# Power.net
KiCad netlist of a schematic drawn in Altium Designer
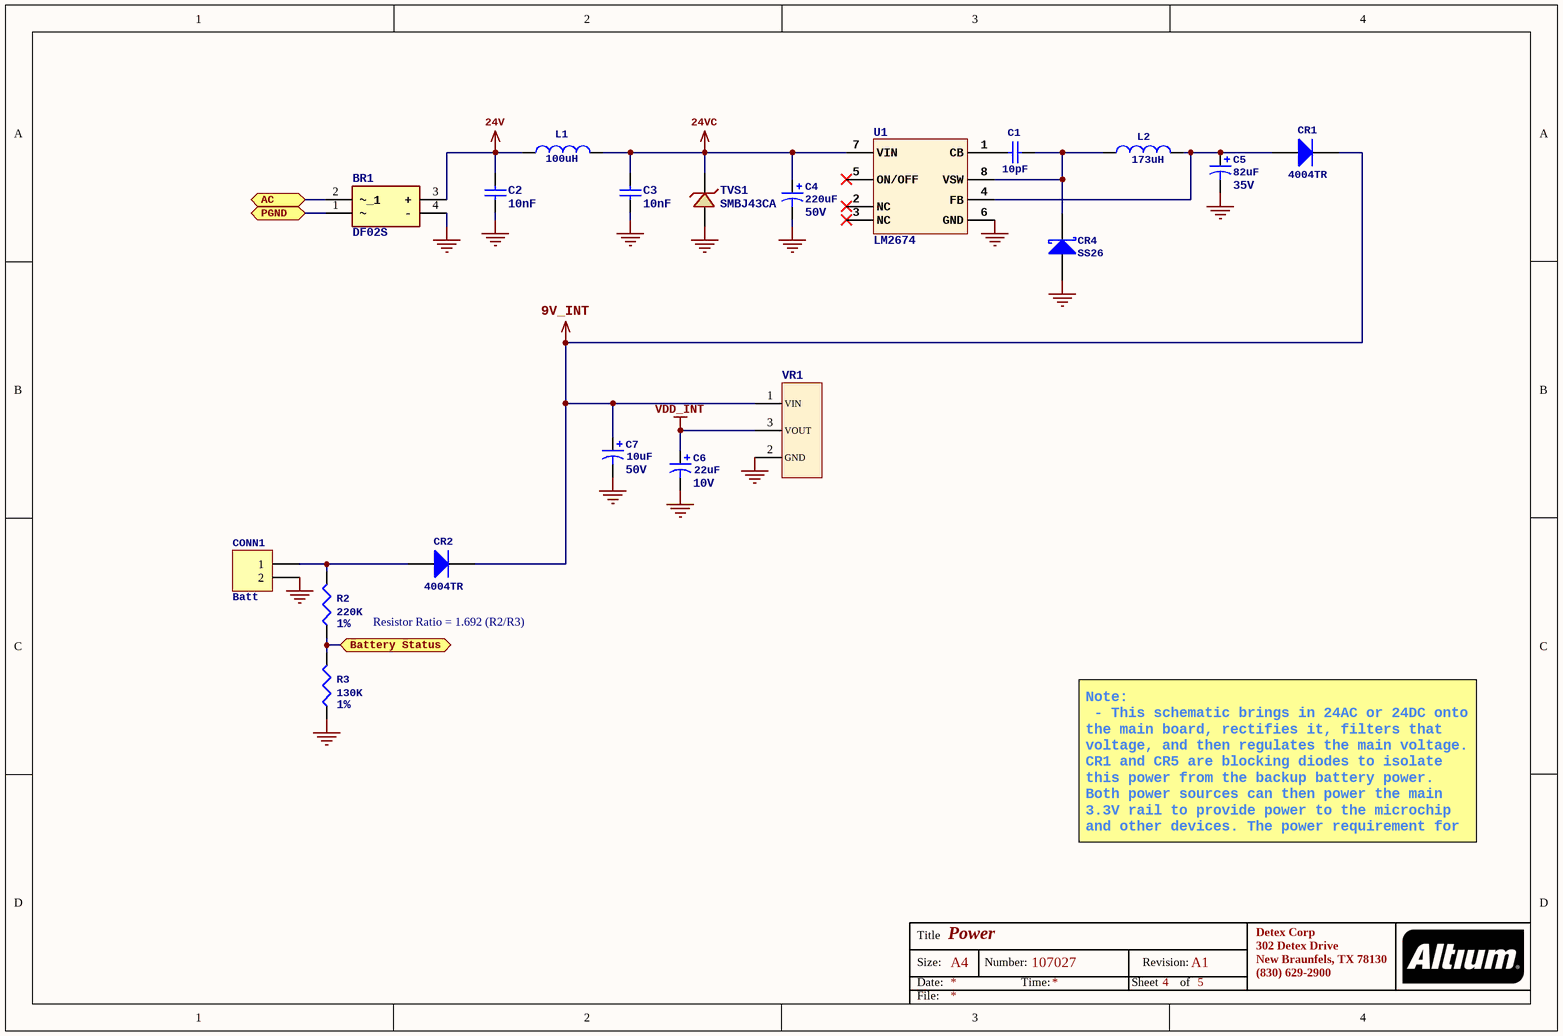
[diagram p0: Power.SchDoc]

(export (version "E")
  (design (tool "Eeschema 10.0.6"))
  (components
    (comp (ref "BR1")
      (value "DF02S")
      (footprint "SamacSys:SOP520P1005X363-4N")
      (description "Bridge Rectifier")
      (fields (field (name "MFR") "Vishay"))
      (libsource (lib "*") (part "DF02S"))
    )
    (comp (ref "C1")
      (value "10pF")
      (footprint "C0805")
      (description "Capacitor")
      (fields (field (name "Comment") "Cap"))
      (libsource (lib "Miscellaneous Devices") (part "Cap"))
    )
    (comp (ref "C2")
      (value "10nF")
      (footprint "C0805")
      (description "Capacitor Ceramic X7R 50V 10nF 0805")
      (fields (field (name "TOLERANCE") "10%") (field (name "Comment") "Cap"))
      (libsource (lib "Altium Concord Pro on Altium 365") (part "CAP-NP-2"))
    )
    (comp (ref "C3")
      (value "10nF")
      (footprint "C0805")
      (description "Capacitor Ceramic X7R 50V 10nF 0805")
      (fields (field (name "TOLERANCE") "10%") (field (name "Comment") "Cap"))
      (libsource (lib "Altium Concord Pro on Altium 365") (part "CAP-NP-2"))
    )
    (comp (ref "C4")
      (value "220uF")
      (footprint "10x12.5 CAP")
      (description "Polarized Capacitor (Surface Mount)")
      (fields (field (name "VOLTAGE") "50V") (field (name "Comment") "Cap Pol3"))
      (libsource (lib "Miscellaneous Devices") (part "Cap Pol3"))
    )
    (comp (ref "C5")
      (value "82uF")
      (footprint "6.3x15 Cap")
      (description "Polarized Capacitor (Surface Mount)")
      (fields
        (field (name "MFR") "Panasonic")
        (field (name "VOLTAGE") "35V")
        (field (name "Comment") "Cap Pol3")
      )
      (libsource (lib "Miscellaneous Devices") (part "Cap Pol3"))
    )
    (comp (ref "C6")
      (value "22uF")
      (footprint "C0805")
      (description "Multilayer Ceramic Capacitors MLCC - SMD/SMT 22UF 10V 20% 0805")
      (fields
        (field (name "MFR") "Murata Electronics")
        (field (name "VOLTAGE") "10V")
        (field (name "Comment") "Cap Pol3")
      )
      (libsource (lib "Miscellaneous Devices") (part "Cap Pol3"))
    )
    (comp (ref "C7")
      (value "10uF")
      (footprint "CAP 1206_3216 - 1.2MM")
      (description "Multilayer Ceramic Capacitors MLCC - SMD/SMT 1206 50V 10uF 10% AEC-Q200")
      (fields (field (name "MFR") "TDK") (field (name "VOLTAGE") "50V") (field (name "Comment") "Cap 1206"))
      (libsource (lib "Miscellaneous Devices") (part "Cap Pol3"))
    )
    (comp (ref "CONN1")
      (value "Batt")
      (footprint "BAT-2")
      (description "Header, 2-Pin")
      (libsource (lib "Miscellaneous Connectors") (part "Header 2"))
    )
    (comp (ref "CR1")
      (value "Diode")
      (footprint "DIODE SMA")
      (description "Default Diode")
      (fields (field (name "MFR P/N") "4004TR"))
      (libsource (lib "Miscellaneous Devices") (part "Diode"))
    )
    (comp (ref "CR2")
      (value "Diode")
      (footprint "DIODE SMA")
      (description "Default Diode")
      (fields (field (name "MFR P/N") "4004TR"))
      (libsource (lib "Miscellaneous Devices") (part "Diode"))
    )
    (comp (ref "CR4")
      (value "D Schottky")
      (footprint "SMB")
      (description "Schottky Barrier Rectifier")
      (fields (field (name "MFR") "VIshay") (field (name "MFR P/N") "SS26"))
      (libsource (lib "Custom Components") (part "D Schottky"))
    )
    (comp (ref "L1")
      (value "100uH")
      (footprint "AXIAL-0.5")
      (description "Inductor")
      (fields (field (name "MFR") "Fastron"))
      (libsource (lib "Miscellaneous Devices") (part "Inductor"))
    )
    (comp (ref "L2")
      (value "173uH")
      (footprint "PE-53819NL")
      (description "Inductor")
      (fields (field (name "MFR") "Pulse"))
      (libsource (lib "Miscellaneous Devices") (part "Inductor"))
    )
    (comp (ref "R2")
      (value "1%")
      (footprint "6-0805_N")
      (description "Resistor 220K Ohm 1% 0805 SMT")
      (fields (field (name "ALTIUM_VALUE") "220K"))
      (libsource (lib "Miscellaneous Devices") (part "Res3"))
    )
    (comp (ref "R3")
      (value "1%")
      (footprint "6-0805_N")
      (description "Resistor 130K Ohm 1% 0805 SMT")
      (fields (field (name "ALTIUM_VALUE") "130K") (field (name "MFR") "Vishay/Dale"))
      (libsource (lib "Miscellaneous Devices") (part "Res3"))
    )
    (comp (ref "TVS1")
      (value "SMBJ43CA")
      (footprint "SMBJSeries_LTF")
      (description "69.4V Clamp 8.7A Ipp Tvs Diode Surface Mount DO-214AA (SMBJ)")
      (fields (field (name "MFR") "Littelfuse Inc"))
      (libsource (lib "Custom Components") (part "SMBJ43CA"))
    )
    (comp (ref "U1")
      (value "LM2674")
      (footprint "SOIC127P600X175-8N")
      (description "IC REG BUCK 12V 0.5A 8-SOIC")
      (libsource (lib "Custom Components") (part "LM2674M-12"))
    )
    (comp (ref "VR1")
      (value "~")
      (footprint "VXO78-1000")
      (fields (field (name "MFR") "CUI"))
      (libsource (lib "Custom Components") (part "DC-DC Converter"))
    )
  )
  (nets
    (net (code "1") (name "/AC") (class "Default")
      (node (ref "BR1") (pin "2") (pinfunction "~_1_2") (pintype "passive"))
    )
    (net (code "2") (name "/Battery Status") (class "Default")
      (node (ref "R2") (pin "1") (pinfunction "1_1") (pintype "passive"))
      (node (ref "R3") (pin "2") (pinfunction "2_2") (pintype "passive"))
    )
    (net (code "3") (name "/PGND") (class "Default")
      (node (ref "BR1") (pin "1") (pinfunction "~_1") (pintype "passive"))
    )
    (net (code "4") (name "9V_INT") (class "Default")
      (node (ref "C7") (pin "1") (pinfunction "1_1") (pintype "passive"))
      (node (ref "CR1") (pin "2") (pinfunction "K_2") (pintype "passive"))
      (node (ref "CR2") (pin "2") (pinfunction "K_2") (pintype "passive"))
      (node (ref "VR1") (pin "1") (pinfunction "VIN_1") (pintype "passive"))
    )
    (net (code "5") (name "24V") (class "Default")
      (node (ref "BR1") (pin "3") (pinfunction "+_3") (pintype "passive"))
      (node (ref "C2") (pin "1") (pinfunction "1_1") (pintype "passive"))
      (node (ref "L1") (pin "1") (pinfunction "1_1") (pintype "passive"))
    )
    (net (code "6") (name "24VC") (class "Default")
      (node (ref "C3") (pin "1") (pinfunction "1_1") (pintype "passive"))
      (node (ref "C4") (pin "1") (pinfunction "1_1") (pintype "passive"))
      (node (ref "L1") (pin "2") (pinfunction "2_2") (pintype "passive"))
      (node (ref "TVS1") (pin "1") (pinfunction "1_1") (pintype "passive"))
      (node (ref "U1") (pin "7") (pinfunction "VIN_7") (pintype "passive"))
    )
    (net (code "7") (name "GND") (class "Default")
      (node (ref "BR1") (pin "4") (pinfunction "-_4") (pintype "passive"))
      (node (ref "C2") (pin "2") (pinfunction "2_2") (pintype "passive"))
      (node (ref "C3") (pin "2") (pinfunction "2_2") (pintype "passive"))
      (node (ref "C4") (pin "2") (pinfunction "2_2") (pintype "passive"))
      (node (ref "C5") (pin "2") (pinfunction "2_2") (pintype "passive"))
      (node (ref "C6") (pin "2") (pinfunction "2_2") (pintype "passive"))
      (node (ref "C7") (pin "2") (pinfunction "2_2") (pintype "passive"))
      (node (ref "CONN1") (pin "2") (pinfunction "2_2") (pintype "passive"))
      (node (ref "CR4") (pin "1") (pinfunction "A_1") (pintype "passive"))
      (node (ref "R3") (pin "1") (pinfunction "1_1") (pintype "passive"))
      (node (ref "TVS1") (pin "2") (pinfunction "2_2") (pintype "passive"))
      (node (ref "U1") (pin "6") (pinfunction "GND_6") (pintype "passive"))
      (node (ref "VR1") (pin "2") (pinfunction "GND_2") (pintype "passive"))
    )
    (net (code "8") (name "Net-(CR1-A)") (class "Default")
      (node (ref "C5") (pin "1") (pinfunction "1_1") (pintype "passive"))
      (node (ref "CR1") (pin "1") (pinfunction "A_1") (pintype "passive"))
      (node (ref "L2") (pin "2") (pinfunction "2_2") (pintype "passive"))
      (node (ref "U1") (pin "4") (pinfunction "FB_4") (pintype "passive"))
    )
    (net (code "9") (name "Net-(CR2-A)") (class "Default")
      (node (ref "CONN1") (pin "1") (pinfunction "1_1") (pintype "passive"))
      (node (ref "CR2") (pin "1") (pinfunction "A_1") (pintype "passive"))
      (node (ref "R2") (pin "2") (pinfunction "2_2") (pintype "passive"))
    )
    (net (code "10") (name "Net-(CR4-K)") (class "Default")
      (node (ref "C1") (pin "1") (pinfunction "1_1") (pintype "passive"))
      (node (ref "CR4") (pin "2") (pinfunction "K_2") (pintype "passive"))
      (node (ref "L2") (pin "1") (pinfunction "1_1") (pintype "passive"))
      (node (ref "U1") (pin "8") (pinfunction "VSW_8") (pintype "passive"))
    )
    (net (code "11") (name "Net-(U1-CB)") (class "Default")
      (node (ref "C1") (pin "2") (pinfunction "2_2") (pintype "passive"))
      (node (ref "U1") (pin "1") (pinfunction "CB_1") (pintype "passive"))
    )
    (net (code "12") (name "VDD_INT") (class "Default")
      (node (ref "C6") (pin "1") (pinfunction "1_1") (pintype "passive"))
      (node (ref "VR1") (pin "3") (pinfunction "VOUT_3") (pintype "passive"))
    )
    (net (code "13") (name "unconnected-(U1-NC-Pad2)") (class "Default")
      (node (ref "U1") (pin "2") (pinfunction "NC_2") (pintype "passive+no_connect"))
    )
    (net (code "14") (name "unconnected-(U1-NC-Pad3)") (class "Default")
      (node (ref "U1") (pin "3") (pinfunction "NC_3") (pintype "passive+no_connect"))
    )
    (net (code "15") (name "unconnected-(U1-ON{slash}OFF-Pad5)") (class "Default")
      (node (ref "U1") (pin "5") (pinfunction "ON/OFF_5") (pintype "passive+no_connect"))
    )
  )
)
